# untitled.net
KiCad netlist of a schematic drawn in EAGLE
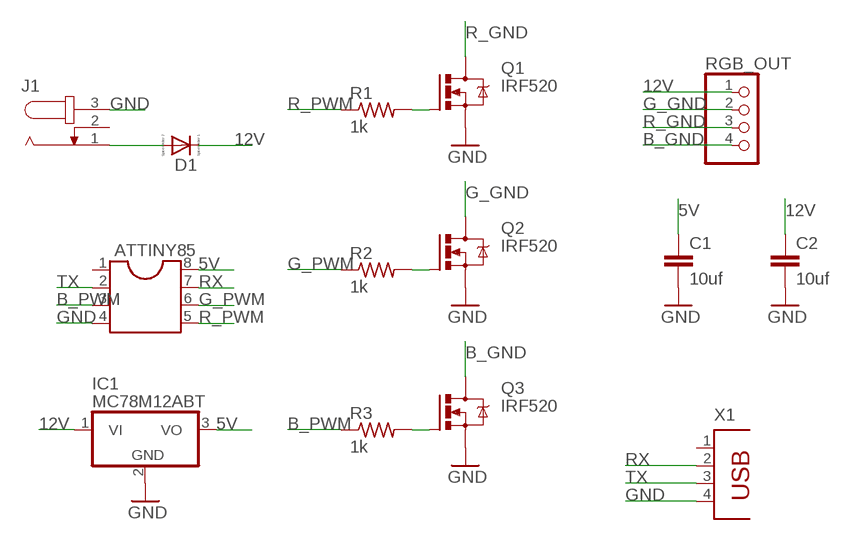
[diagram p0: schematic, sheet 1]

(export (version "E")
  (design (tool "Eeschema 10.0.6"))
  (components
    (comp (ref "ATTINY85")
      (value "DIL8S")
      (footprint "eagle-import:SOCKET-08")
      (libsource (lib "eagle-import") (part "DIL8S"))
    )
    (comp (ref "C1")
      (value "10uf")
      (footprint "eagle-import:C050-045X075")
      (libsource (lib "eagle-import") (part "C-EU050-045X075"))
    )
    (comp (ref "C2")
      (value "10uf")
      (footprint "eagle-import:C050-045X075")
      (libsource (lib "eagle-import") (part "C-EU050-045X075"))
    )
    (comp (ref "D1")
      (value "DIODE_E-DO35-7")
      (footprint "eagle-import:DIODE_DO35-7")
      (libsource (lib "eagle-import") (part "DIODE_E-DO35-7"))
    )
    (comp (ref "IC1")
      (value "MC78M12ABT")
      (footprint "eagle-import:TO220V")
      (libsource (lib "eagle-import") (part "MC78MT12AB"))
    )
    (comp (ref "J1")
      (value "JACK-PLUG0")
      (footprint "eagle-import:SPC4077")
      (libsource (lib "eagle-import") (part "JACK-PLUG0"))
    )
    (comp (ref "Q1")
      (value "IRF520")
      (footprint "eagle-import:TO220BV")
      (libsource (lib "eagle-import") (part "IRF520"))
    )
    (comp (ref "Q2")
      (value "IRF520")
      (footprint "eagle-import:TO220BV")
      (libsource (lib "eagle-import") (part "IRF520"))
    )
    (comp (ref "Q3")
      (value "IRF520")
      (footprint "eagle-import:TO220BV")
      (libsource (lib "eagle-import") (part "IRF520"))
    )
    (comp (ref "R1")
      (value "1k")
      (footprint "eagle-import:0207_10")
      (libsource (lib "eagle-import") (part "R-US_0207/10"))
    )
    (comp (ref "R2")
      (value "1k")
      (footprint "eagle-import:0207_10")
      (libsource (lib "eagle-import") (part "R-US_0207/10"))
    )
    (comp (ref "R3")
      (value "1k")
      (footprint "eagle-import:0207_10")
      (libsource (lib "eagle-import") (part "R-US_0207/10"))
    )
    (comp (ref "RGB_OUT")
      (value "PINHD-1X4")
      (footprint "eagle-import:1X04")
      (libsource (lib "eagle-import") (part "PINHD-1X4"))
    )
    (comp (ref "X1")
      (value "PN87520")
      (footprint "eagle-import:PN87520")
      (libsource (lib "eagle-import") (part "PN87520"))
    )
  )
  (nets
    (net (code "1") (name "/5V") (class "Default")
      (node (ref "ATTINY85") (pin "8") (pinfunction "8_8") (pintype "passive"))
      (node (ref "C1") (pin "1") (pinfunction "1_1") (pintype "passive"))
      (node (ref "IC1") (pin "3") (pinfunction "VO_3") (pintype "passive"))
    )
    (net (code "2") (name "/12V") (class "Default")
      (node (ref "C2") (pin "1") (pinfunction "1_1") (pintype "passive"))
      (node (ref "D1") (pin "C") (pinfunction "A_C") (pintype "passive"))
      (node (ref "IC1") (pin "1") (pinfunction "VI_1") (pintype "input"))
      (node (ref "RGB_OUT") (pin "1") (pinfunction "1_1") (pintype "passive"))
    )
    (net (code "3") (name "/B_GND") (class "Default")
      (node (ref "Q3") (pin "D") (pinfunction "D_D") (pintype "passive"))
      (node (ref "RGB_OUT") (pin "4") (pinfunction "4_4") (pintype "passive"))
    )
    (net (code "4") (name "/B_PWM") (class "Default")
      (node (ref "ATTINY85") (pin "3") (pinfunction "3_3") (pintype "passive"))
      (node (ref "R3") (pin "1") (pinfunction "1_1") (pintype "passive"))
    )
    (net (code "5") (name "/G_GND") (class "Default")
      (node (ref "Q2") (pin "D") (pinfunction "D_D") (pintype "passive"))
      (node (ref "RGB_OUT") (pin "2") (pinfunction "2_2") (pintype "passive"))
    )
    (net (code "6") (name "/G_PWM") (class "Default")
      (node (ref "ATTINY85") (pin "6") (pinfunction "6_6") (pintype "passive"))
      (node (ref "R2") (pin "1") (pinfunction "1_1") (pintype "passive"))
    )
    (net (code "7") (name "/RX") (class "Default")
      (node (ref "ATTINY85") (pin "7") (pinfunction "7_7") (pintype "passive"))
      (node (ref "X1") (pin "2") (pinfunction "2_2") (pintype "passive"))
    )
    (net (code "8") (name "/R_GND") (class "Default")
      (node (ref "Q1") (pin "D") (pinfunction "D_D") (pintype "passive"))
      (node (ref "RGB_OUT") (pin "3") (pinfunction "3_3") (pintype "passive"))
    )
    (net (code "9") (name "/R_PWM") (class "Default")
      (node (ref "ATTINY85") (pin "5") (pinfunction "5_5") (pintype "passive"))
      (node (ref "R1") (pin "1") (pinfunction "1_1") (pintype "passive"))
    )
    (net (code "10") (name "/TX") (class "Default")
      (node (ref "ATTINY85") (pin "2") (pinfunction "2_2") (pintype "passive"))
      (node (ref "X1") (pin "3") (pinfunction "3_3") (pintype "passive"))
    )
    (net (code "11") (name "GND") (class "Default")
      (node (ref "ATTINY85") (pin "4") (pinfunction "4_4") (pintype "passive"))
      (node (ref "C1") (pin "2") (pinfunction "2_2") (pintype "passive"))
      (node (ref "C2") (pin "2") (pinfunction "2_2") (pintype "passive"))
      (node (ref "IC1") (pin "2") (pinfunction "GND_2") (pintype "passive"))
      (node (ref "J1") (pin "3") (pinfunction "3_3") (pintype "passive"))
      (node (ref "Q1") (pin "S") (pinfunction "S_S") (pintype "passive"))
      (node (ref "Q2") (pin "S") (pinfunction "S_S") (pintype "passive"))
      (node (ref "Q3") (pin "S") (pinfunction "S_S") (pintype "passive"))
      (node (ref "X1") (pin "4") (pinfunction "4_4") (pintype "passive"))
    )
    (net (code "12") (name "Net-(D1-C)") (class "Default")
      (node (ref "D1") (pin "A") (pinfunction "C_A") (pintype "passive"))
      (node (ref "J1") (pin "1") (pinfunction "1_1") (pintype "passive"))
    )
    (net (code "13") (name "Net-(Q1-PadG)") (class "Default")
      (node (ref "Q1") (pin "G") (pinfunction "G_G") (pintype "passive"))
      (node (ref "R1") (pin "2") (pinfunction "2_2") (pintype "passive"))
    )
    (net (code "14") (name "Net-(Q2-PadG)") (class "Default")
      (node (ref "Q2") (pin "G") (pinfunction "G_G") (pintype "passive"))
      (node (ref "R2") (pin "2") (pinfunction "2_2") (pintype "passive"))
    )
    (net (code "15") (name "Net-(Q3-PadG)") (class "Default")
      (node (ref "Q3") (pin "G") (pinfunction "G_G") (pintype "passive"))
      (node (ref "R3") (pin "2") (pinfunction "2_2") (pintype "passive"))
    )
    (net (code "16") (name "unconnected-(ATTINY85-Pad1)") (class "Default")
      (node (ref "ATTINY85") (pin "1") (pinfunction "1_1") (pintype "passive"))
    )
    (net (code "17") (name "unconnected-(J1-Pad2)") (class "Default")
      (node (ref "J1") (pin "2") (pinfunction "2_2") (pintype "passive"))
    )
    (net (code "18") (name "unconnected-(X1-Pad1)") (class "Default")
      (node (ref "X1") (pin "1") (pinfunction "1_1") (pintype "passive"))
    )
  )
)
